# 08-modem2.net
KiCad netlist of a schematic drawn in Altium Designer
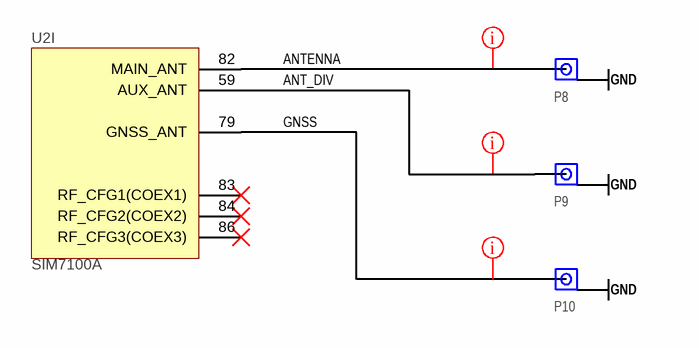
[diagram p0: 08-modem2.SchDoc]

(export (version "E")
  (design (tool "Eeschema 10.0.6"))
  (components
    (comp (ref "P8")
      (value "U.FL-R-SMT(10)")
      (footprint "U.FL-R-SMT(10)")
      (description "Ultra Miniature Coaxial Jack, 50 Ohms")
      (fields (field (name "MANUFACTURER") "Hirose"))
      (libsource (lib "hirose") (part "U.FL-R-SMT(10)"))
    )
    (comp (ref "P9")
      (value "U.FL-R-SMT(10)")
      (footprint "U.FL-R-SMT(10)")
      (description "Ultra Miniature Coaxial Jack, 50 Ohms")
      (fields (field (name "MANUFACTURER") "Hirose"))
      (libsource (lib "hirose") (part "U.FL-R-SMT(10)"))
    )
    (comp (ref "P10")
      (value "U.FL-R-SMT(10)")
      (footprint "U.FL-R-SMT(10)")
      (description "Ultra Miniature Coaxial Jack, 50 Ohms")
      (fields (field (name "MANUFACTURER") "Hirose"))
      (libsource (lib "hirose") (part "U.FL-R-SMT(10)"))
    )
    (comp (ref "U2")
      (value "SIM7100A")
      (footprint "SIM7100A")
      (description "Cellular Module")
      (fields (field (name "MANUFACTURER") "SIMCOM"))
      (libsource (lib "simcom") (part "Component_1"))
    )
  )
  (nets
    (net (code "1") (name "/ANTENNA") (class "Default")
      (node (ref "P8") (pin "1") (pinfunction "RF_1") (pintype "passive"))
      (node (ref "U2") (pin "82") (pinfunction "MAIN_ANT_82") (pintype "passive"))
    )
    (net (code "2") (name "/ANT_DIV") (class "Default")
      (node (ref "P9") (pin "1") (pinfunction "RF_1") (pintype "passive"))
      (node (ref "U2") (pin "59") (pinfunction "AUX_ANT_59") (pintype "passive"))
    )
    (net (code "3") (name "/GNSS") (class "Default")
      (node (ref "P10") (pin "1") (pinfunction "RF_1") (pintype "passive"))
      (node (ref "U2") (pin "79") (pinfunction "GNSS_ANT_79") (pintype "passive"))
    )
    (net (code "4") (name "GND") (class "Default")
      (node (ref "P10") (pin "2") (pinfunction "GND_2") (pintype "passive"))
      (node (ref "P8") (pin "2") (pinfunction "GND_2") (pintype "passive"))
      (node (ref "P9") (pin "2") (pinfunction "GND_2") (pintype "passive"))
    )
    (net (code "5") (name "unconnected-(U2I-RF_CFG1(COEX1)-Pad83)") (class "Default")
      (node (ref "U2") (pin "83") (pinfunction "RF_CFG1(COEX1)_83") (pintype "passive+no_connect"))
    )
    (net (code "6") (name "unconnected-(U2I-RF_CFG2(COEX2)-Pad84)") (class "Default")
      (node (ref "U2") (pin "84") (pinfunction "RF_CFG2(COEX2)_84") (pintype "passive+no_connect"))
    )
    (net (code "7") (name "unconnected-(U2I-RF_CFG3(COEX3)-Pad86)") (class "Default")
      (node (ref "U2") (pin "86") (pinfunction "RF_CFG3(COEX3)_86") (pintype "passive+no_connect"))
    )
  )
)
